# User_Button_Panel.net
KiCad netlist of a schematic drawn in Altium Designer
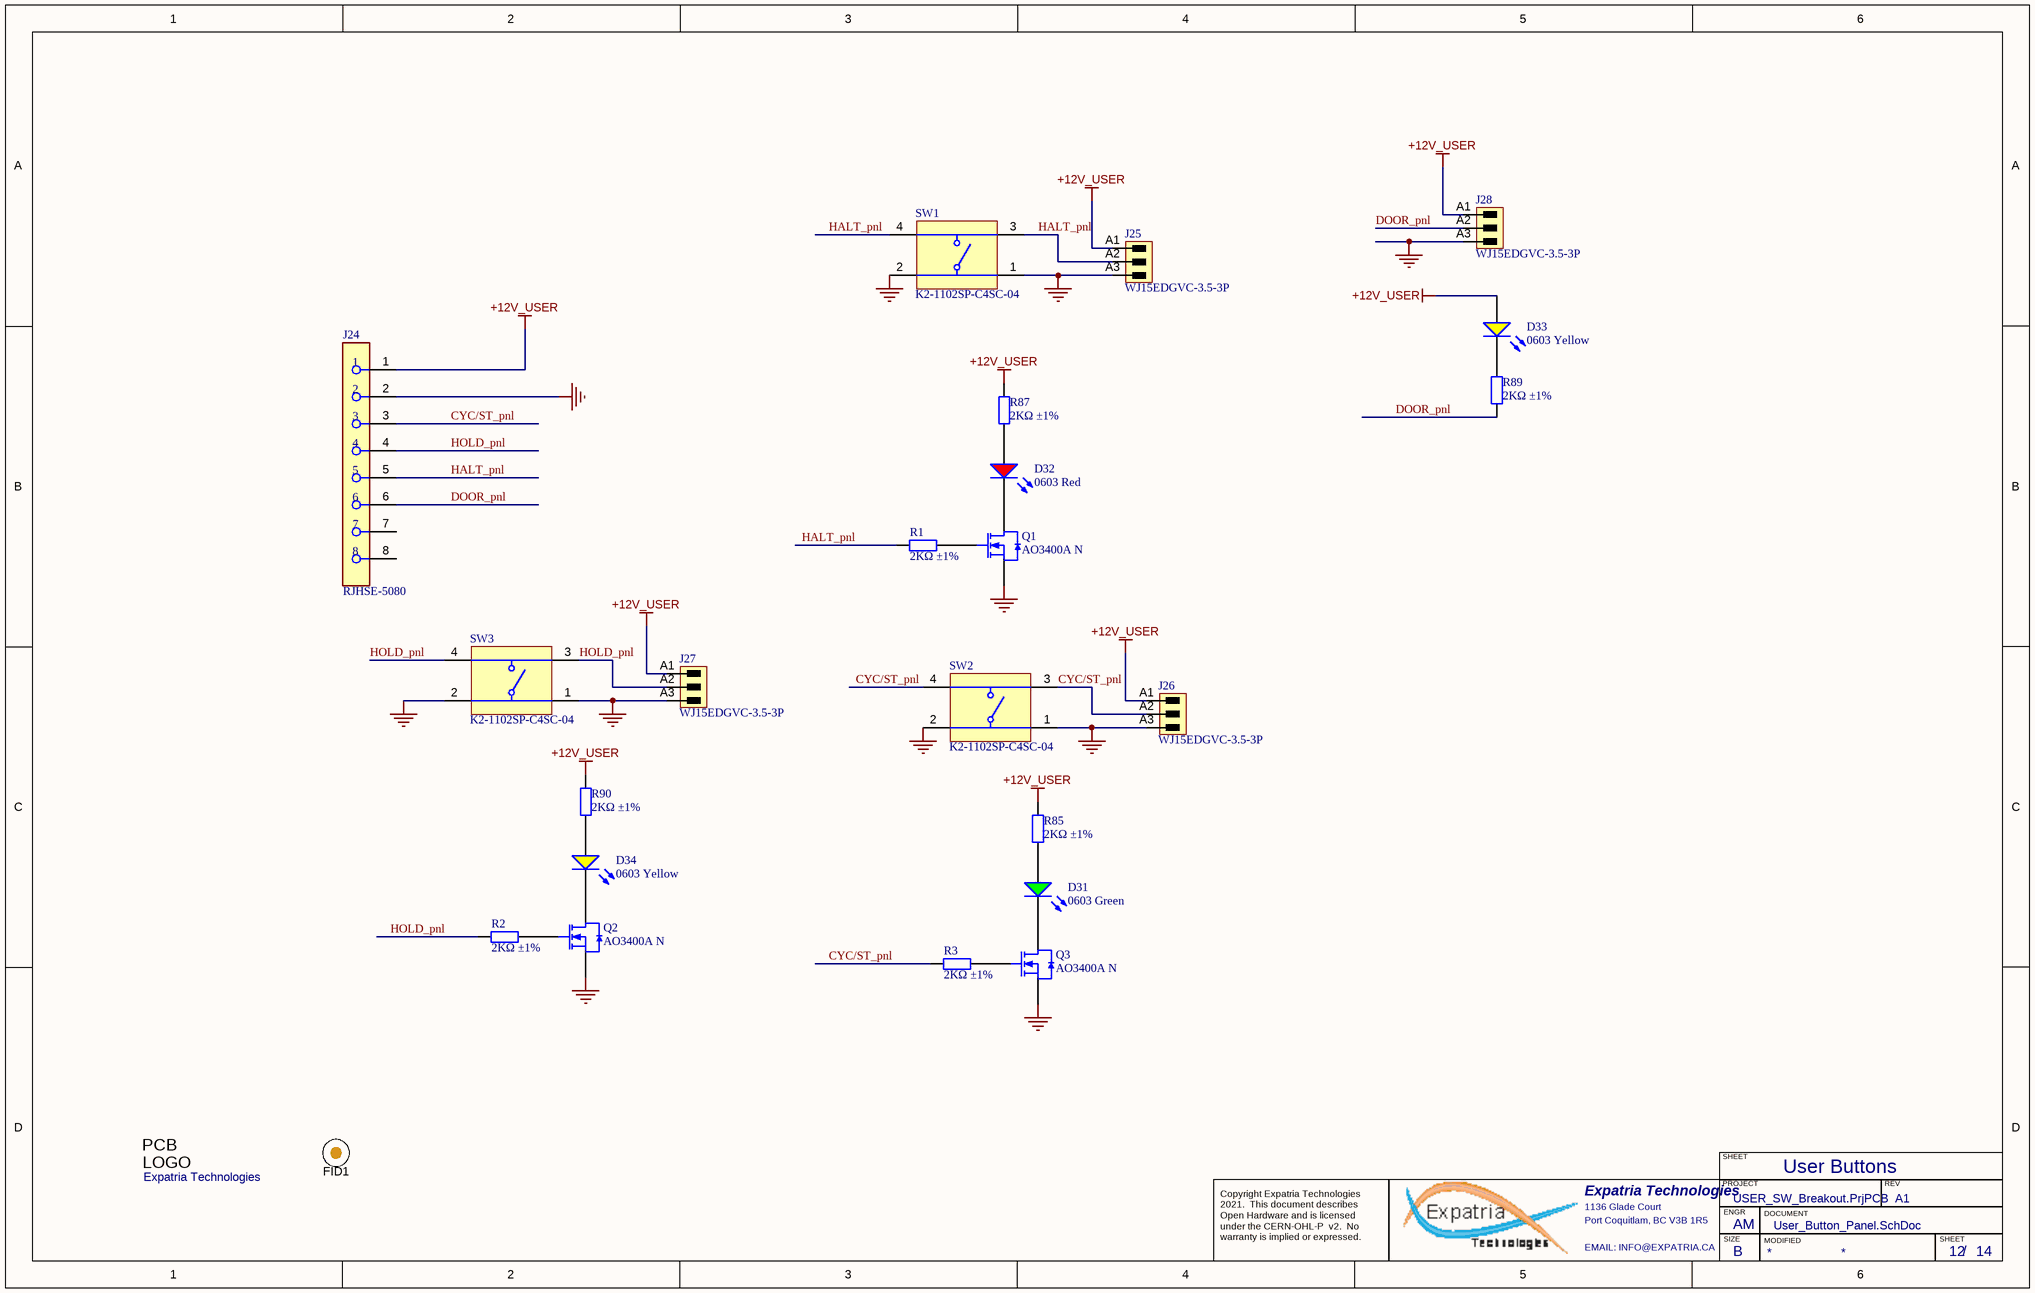
[diagram p0: User_Button_Panel.SchDoc]

(export (version "E")
  (design (tool "Eeschema 10.0.6"))
  (components
    (comp (ref "D31")
      (value "0603 Green")
      (footprint "0603_LED_S1")
      (description "LED")
      (libsource (lib "LED") (part "0603 LED Green"))
    )
    (comp (ref "D32")
      (value "0603 Red")
      (footprint "0603_LED_S1")
      (description "LED")
      (libsource (lib "LED") (part "0603 LED Red"))
    )
    (comp (ref "D33")
      (value "0603 Yellow")
      (footprint "0603_LED_S1")
      (description "LED")
      (libsource (lib "LED") (part "0603 LED Yellow"))
    )
    (comp (ref "D34")
      (value "0603 Yellow")
      (footprint "0603_LED_S1")
      (description "LED")
      (libsource (lib "LED") (part "0603 LED Yellow"))
    )
    (comp (ref "FID1")
      (value "Fiducial")
      (footprint "Fiducial10-20")
      (description "FIDUCIAL NO ASSEMBLY")
      (libsource (lib "GLMR") (part "Fiducial"))
    )
    (comp (ref "J24")
      (value "RJHSE-5080")
      (footprint "FP-RJHSE-5080-MFG")
      (description "CONN MOD JACK 8P8C R/A UNSHLD")
      (fields
        (field (name "MANUFACTURER PART NUMBER") "E5J88-00LJG2-L")
        (field (name "MANUFACTURER") "Pulse Electronics Network")
      )
      (libsource (lib "Altium Content Vault") (part "b0a0b555dd3abf3683e7c330df25cc4"))
    )
    (comp (ref "J25")
      (value "WJ15EDGVC-3.5-3P")
      (footprint "SL_3_50_180G_03")
      (fields (field (name "MANUFACTURER") "Ningbo Kangnex Elec"))
      (libsource (lib "PrintNC_GRBLHAL_Breakout") (part "Header_Male_03_1x03"))
    )
    (comp (ref "J26")
      (value "WJ15EDGVC-3.5-3P")
      (footprint "SL_3_50_180G_03")
      (fields (field (name "MANUFACTURER") "Ningbo Kangnex Elec"))
      (libsource (lib "PrintNC_GRBLHAL_Breakout") (part "Header_Male_03_1x03"))
    )
    (comp (ref "J27")
      (value "WJ15EDGVC-3.5-3P")
      (footprint "SL_3_50_180G_03")
      (fields (field (name "MANUFACTURER") "Ningbo Kangnex Elec"))
      (libsource (lib "PrintNC_GRBLHAL_Breakout") (part "Header_Male_03_1x03"))
    )
    (comp (ref "J28")
      (value "WJ15EDGVC-3.5-3P")
      (footprint "SL_3_50_180G_03")
      (fields (field (name "MANUFACTURER") "Ningbo Kangnex Elec"))
      (libsource (lib "PrintNC_GRBLHAL_Breakout") (part "Header_Male_03_1x03"))
    )
    (comp (ref "Logo1")
      (value "Expatria Technologies")
      (footprint "Expatria-Logo")
      (libsource (lib "PrintNC_GRBLHAL_Breakout") (part "SBT-Logo"))
    )
    (comp (ref "Q1")
      (value "AO3400A N")
      (footprint "SOT-23-3L")
      (description "MOS(场效应管)")
      (libsource (lib "MOS") (part "AO3400A N道沟 X0YV1T SOT-23"))
    )
    (comp (ref "Q2")
      (value "AO3400A N")
      (footprint "SOT-23-3L")
      (description "MOS(场效应管)")
      (libsource (lib "MOS") (part "AO3400A N道沟 X0YV1T SOT-23"))
    )
    (comp (ref "Q3")
      (value "AO3400A N")
      (footprint "SOT-23-3L")
      (description "MOS(场效应管)")
      (libsource (lib "MOS") (part "AO3400A N道沟 X0YV1T SOT-23"))
    )
    (comp (ref "R1")
      (value "2KΩ ±1%")
      (footprint "0603_R")
      (description "Chip resistor")
      (fields (field (name "MANUFACTURER") "Uniroyal Elec") (field (name "PARTNUMBER") "0603WAF2001T5E"))
      (libsource (lib "PrintNC_GRBLHAL_Breakout") (part "0603 2K (2001) 1%"))
    )
    (comp (ref "R2")
      (value "2KΩ ±1%")
      (footprint "0603_R")
      (description "Chip resistor")
      (fields (field (name "MANUFACTURER") "Uniroyal Elec") (field (name "PARTNUMBER") "0603WAF2001T5E"))
      (libsource (lib "PrintNC_GRBLHAL_Breakout") (part "0603 2K (2001) 1%"))
    )
    (comp (ref "R3")
      (value "2KΩ ±1%")
      (footprint "0603_R")
      (description "Chip resistor")
      (fields (field (name "MANUFACTURER") "Uniroyal Elec") (field (name "PARTNUMBER") "0603WAF2001T5E"))
      (libsource (lib "PrintNC_GRBLHAL_Breakout") (part "0603 2K (2001) 1%"))
    )
    (comp (ref "R85")
      (value "2KΩ ±1%")
      (footprint "0603_R")
      (description "Chip resistor")
      (fields (field (name "MANUFACTURER") "Uniroyal Elec") (field (name "PARTNUMBER") "0603WAF2001T5E"))
      (libsource (lib "") (part "0603 2K (2001) 1%_1"))
    )
    (comp (ref "R87")
      (value "2KΩ ±1%")
      (footprint "0603_R")
      (description "Chip resistor")
      (fields (field (name "MANUFACTURER") "Uniroyal Elec") (field (name "PARTNUMBER") "0603WAF2001T5E"))
      (libsource (lib "") (part "0603 2K (2001) 1%_2"))
    )
    (comp (ref "R89")
      (value "2KΩ ±1%")
      (footprint "0603_R")
      (description "Chip resistor")
      (fields (field (name "MANUFACTURER") "Uniroyal Elec") (field (name "PARTNUMBER") "0603WAF2001T5E"))
      (libsource (lib "") (part "0603 2K (2001) 1%_2"))
    )
    (comp (ref "R90")
      (value "2KΩ ±1%")
      (footprint "0603_R")
      (description "Chip resistor")
      (fields (field (name "MANUFACTURER") "Uniroyal Elec") (field (name "PARTNUMBER") "0603WAF2001T5E"))
      (libsource (lib "") (part "0603 2K (2001) 1%_2"))
    )
    (comp (ref "SW1")
      (value "K2-1102SP-C4SC-04")
      (footprint "TECO-FSM4JSMATR_V")
      (description "Top Actuated 50mA @ 12VDC Round Button SPST 6*6mm Tactile Switches ROHS")
      (libsource (lib "Altium Content Vault") (part "SW-SPST-4_A"))
    )
    (comp (ref "SW2")
      (value "K2-1102SP-C4SC-04")
      (footprint "TECO-FSM4JSMATR_V")
      (description "Top Actuated 50mA @ 12VDC Round Button SPST 6*6mm Tactile Switches ROHS")
      (libsource (lib "Altium Content Vault") (part "SW-SPST-4_A"))
    )
    (comp (ref "SW3")
      (value "K2-1102SP-C4SC-04")
      (footprint "TECO-FSM4JSMATR_V")
      (description "Top Actuated 50mA @ 12VDC Round Button SPST 6*6mm Tactile Switches ROHS")
      (libsource (lib "Altium Content Vault") (part "SW-SPST-4_A"))
    )
  )
  (nets
    (net (code "1") (name "+12V_USER") (class "Default")
      (node (ref "D33") (pin "A") (pinfunction "A_A") (pintype "passive"))
      (node (ref "J24") (pin "1") (pinfunction "1_1") (pintype "passive"))
      (node (ref "J25") (pin "A1") (pinfunction "A1_A1") (pintype "passive"))
      (node (ref "J26") (pin "A1") (pinfunction "A1_A1") (pintype "passive"))
      (node (ref "J27") (pin "A1") (pinfunction "A1_A1") (pintype "passive"))
      (node (ref "J28") (pin "A1") (pinfunction "A1_A1") (pintype "passive"))
      (node (ref "R85") (pin "2") (pinfunction "2_2") (pintype "passive"))
      (node (ref "R87") (pin "1") (pinfunction "1_1") (pintype "passive"))
      (node (ref "R90") (pin "1") (pinfunction "1_1") (pintype "passive"))
    )
    (net (code "2") (name "/CYC{slash}ST_pnl") (class "Default")
      (node (ref "J24") (pin "3") (pinfunction "3_3") (pintype "passive"))
      (node (ref "J26") (pin "A2") (pinfunction "A2_A2") (pintype "passive"))
      (node (ref "R3") (pin "2") (pinfunction "2_2") (pintype "passive"))
      (node (ref "SW2") (pin "3") (pinfunction "3_3") (pintype "passive"))
      (node (ref "SW2") (pin "4") (pinfunction "4_4") (pintype "passive"))
    )
    (net (code "3") (name "/DOOR_pnl") (class "Default")
      (node (ref "J24") (pin "6") (pinfunction "6_6") (pintype "passive"))
      (node (ref "J28") (pin "A2") (pinfunction "A2_A2") (pintype "passive"))
      (node (ref "R89") (pin "2") (pinfunction "2_2") (pintype "passive"))
    )
    (net (code "4") (name "/HALT_pnl") (class "Default")
      (node (ref "J24") (pin "5") (pinfunction "5_5") (pintype "passive"))
      (node (ref "J25") (pin "A2") (pinfunction "A2_A2") (pintype "passive"))
      (node (ref "R1") (pin "2") (pinfunction "2_2") (pintype "passive"))
      (node (ref "SW1") (pin "3") (pinfunction "3_3") (pintype "passive"))
      (node (ref "SW1") (pin "4") (pinfunction "4_4") (pintype "passive"))
    )
    (net (code "5") (name "/HOLD_pnl") (class "Default")
      (node (ref "J24") (pin "4") (pinfunction "4_4") (pintype "passive"))
      (node (ref "J27") (pin "A2") (pinfunction "A2_A2") (pintype "passive"))
      (node (ref "R2") (pin "2") (pinfunction "2_2") (pintype "passive"))
      (node (ref "SW3") (pin "3") (pinfunction "3_3") (pintype "passive"))
      (node (ref "SW3") (pin "4") (pinfunction "4_4") (pintype "passive"))
    )
    (net (code "6") (name "GND_USER") (class "Default")
      (node (ref "J24") (pin "2") (pinfunction "2_2") (pintype "passive"))
      (node (ref "J25") (pin "A3") (pinfunction "A3_A3") (pintype "passive"))
      (node (ref "J26") (pin "A3") (pinfunction "A3_A3") (pintype "passive"))
      (node (ref "J27") (pin "A3") (pinfunction "A3_A3") (pintype "passive"))
      (node (ref "J28") (pin "A3") (pinfunction "A3_A3") (pintype "passive"))
      (node (ref "Q1") (pin "2") (pinfunction "S_2") (pintype "passive"))
      (node (ref "Q2") (pin "2") (pinfunction "S_2") (pintype "passive"))
      (node (ref "Q3") (pin "2") (pinfunction "S_2") (pintype "passive"))
      (node (ref "SW1") (pin "1") (pinfunction "1_1") (pintype "passive"))
      (node (ref "SW1") (pin "2") (pinfunction "2_2") (pintype "passive"))
      (node (ref "SW2") (pin "1") (pinfunction "1_1") (pintype "passive"))
      (node (ref "SW2") (pin "2") (pinfunction "2_2") (pintype "passive"))
      (node (ref "SW3") (pin "1") (pinfunction "1_1") (pintype "passive"))
      (node (ref "SW3") (pin "2") (pinfunction "2_2") (pintype "passive"))
    )
    (net (code "7") (name "Net-(D31-PadA)") (class "Default")
      (node (ref "D31") (pin "A") (pinfunction "A_A") (pintype "passive"))
      (node (ref "R85") (pin "1") (pinfunction "1_1") (pintype "passive"))
    )
    (net (code "8") (name "Net-(D32-PadA)") (class "Default")
      (node (ref "D32") (pin "A") (pinfunction "A_A") (pintype "passive"))
      (node (ref "R87") (pin "2") (pinfunction "2_2") (pintype "passive"))
    )
    (net (code "9") (name "Net-(D33-PadK)") (class "Default")
      (node (ref "D33") (pin "K") (pinfunction "K_K") (pintype "passive"))
      (node (ref "R89") (pin "1") (pinfunction "1_1") (pintype "passive"))
    )
    (net (code "10") (name "Net-(D34-PadA)") (class "Default")
      (node (ref "D34") (pin "A") (pinfunction "A_A") (pintype "passive"))
      (node (ref "R90") (pin "2") (pinfunction "2_2") (pintype "passive"))
    )
    (net (code "11") (name "Net-(Q1-D)") (class "Default")
      (node (ref "D32") (pin "K") (pinfunction "K_K") (pintype "passive"))
      (node (ref "Q1") (pin "3") (pinfunction "D_3") (pintype "passive"))
    )
    (net (code "12") (name "Net-(Q1-G)") (class "Default")
      (node (ref "Q1") (pin "1") (pinfunction "G_1") (pintype "passive"))
      (node (ref "R1") (pin "1") (pinfunction "1_1") (pintype "passive"))
    )
    (net (code "13") (name "Net-(Q2-D)") (class "Default")
      (node (ref "D34") (pin "K") (pinfunction "K_K") (pintype "passive"))
      (node (ref "Q2") (pin "3") (pinfunction "D_3") (pintype "passive"))
    )
    (net (code "14") (name "Net-(Q2-G)") (class "Default")
      (node (ref "Q2") (pin "1") (pinfunction "G_1") (pintype "passive"))
      (node (ref "R2") (pin "1") (pinfunction "1_1") (pintype "passive"))
    )
    (net (code "15") (name "Net-(Q3-D)") (class "Default")
      (node (ref "D31") (pin "K") (pinfunction "K_K") (pintype "passive"))
      (node (ref "Q3") (pin "3") (pinfunction "D_3") (pintype "passive"))
    )
    (net (code "16") (name "Net-(Q3-G)") (class "Default")
      (node (ref "Q3") (pin "1") (pinfunction "G_1") (pintype "passive"))
      (node (ref "R3") (pin "1") (pinfunction "1_1") (pintype "passive"))
    )
    (net (code "17") (name "unconnected-(J24-Pad7)") (class "Default")
      (node (ref "J24") (pin "7") (pinfunction "7_7") (pintype "passive"))
    )
    (net (code "18") (name "unconnected-(J24-Pad8)") (class "Default")
      (node (ref "J24") (pin "8") (pinfunction "8_8") (pintype "passive"))
    )
  )
)
